# Sheet1.net
KiCad netlist of a schematic drawn in Altium Designer
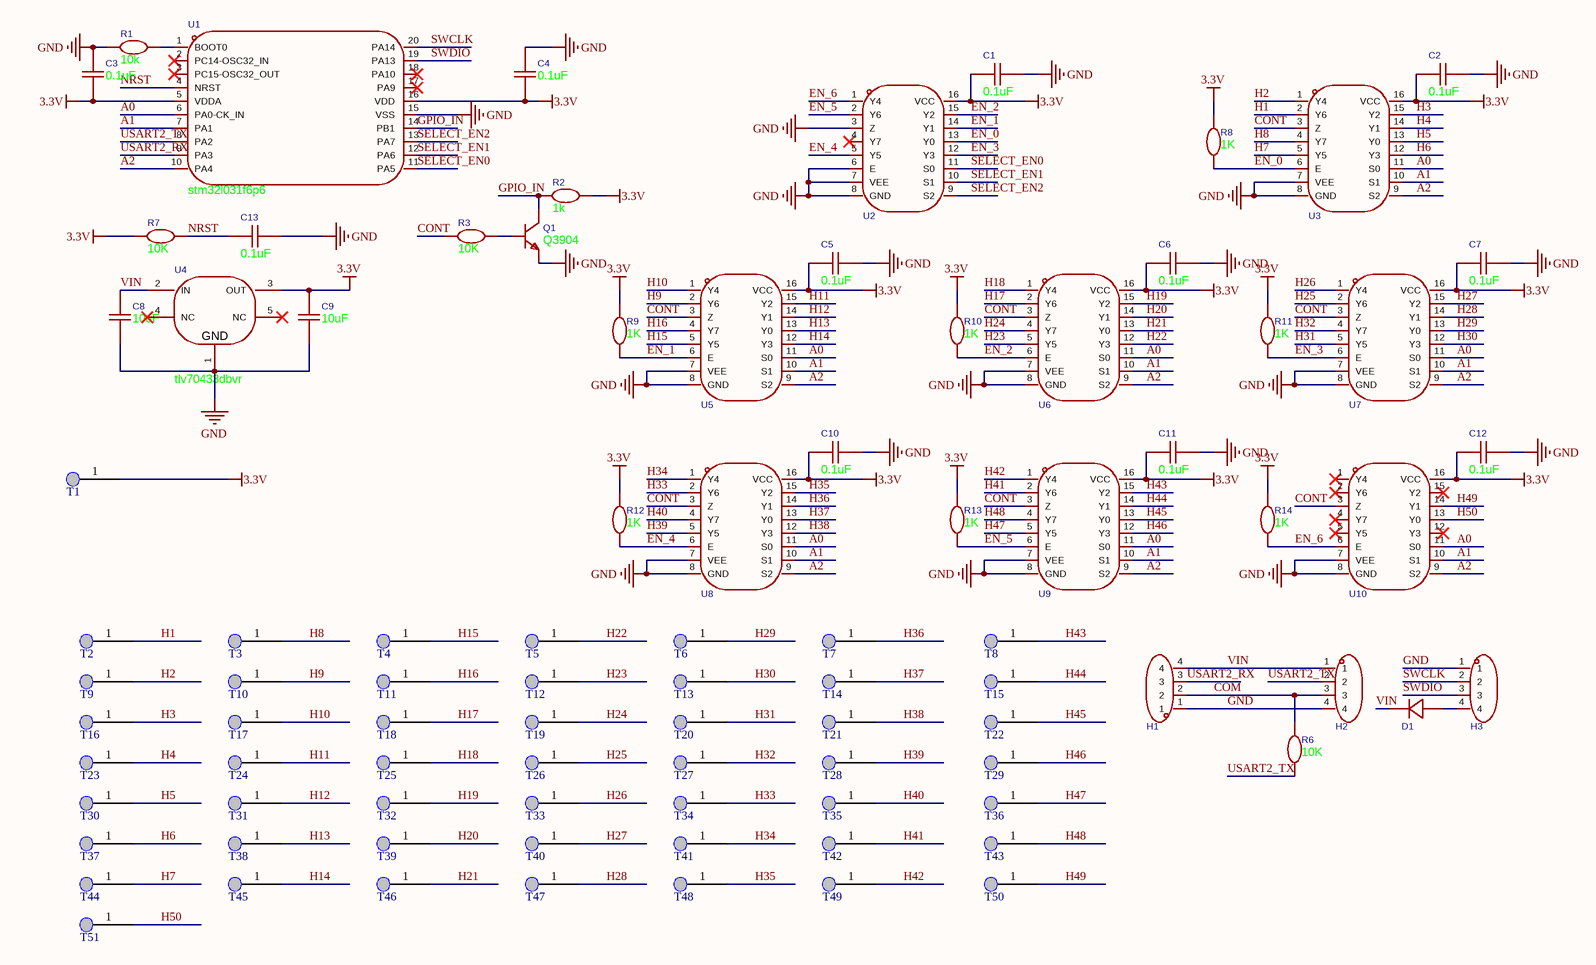
[diagram p0: Sheet1.SchDoc]

(export (version "E")
  (design (tool "Eeschema 10.0.6"))
  (components
    (comp (ref "C1")
      (value "0.1uF")
      (footprint "C0603")
      (description "容值:100nF;精度:±10%;额定电压:50V;温度系数:X7R;")
      (fields (field (name "MANUFACTURER") "SAMSUNG(三星)") (field (name "MANUFACTURERPART") "CL10B104KB8NNNC"))
      (libsource (lib "Schlib1") (part "C"))
    )
    (comp (ref "C2")
      (value "0.1uF")
      (footprint "C0603")
      (description "容值:100nF;精度:±10%;额定电压:50V;温度系数:X7R;")
      (fields (field (name "MANUFACTURER") "SAMSUNG(三星)") (field (name "MANUFACTURERPART") "CL10B104KB8NNNC"))
      (libsource (lib "Schlib1") (part "C"))
    )
    (comp (ref "C3")
      (value "0.1uF")
      (footprint "C0603")
      (description "容值:100nF;精度:±10%;额定电压:50V;温度系数:X7R;")
      (fields (field (name "MANUFACTURER") "SAMSUNG(三星)") (field (name "MANUFACTURERPART") "CL10B104KB8NNNC"))
      (libsource (lib "Schlib1") (part "C"))
    )
    (comp (ref "C4")
      (value "0.1uF")
      (footprint "C0603")
      (description "容值:100nF;精度:±10%;额定电压:50V;温度系数:X7R;")
      (fields (field (name "MANUFACTURER") "SAMSUNG(三星)") (field (name "MANUFACTURERPART") "CL10B104KB8NNNC"))
      (libsource (lib "Schlib1") (part "C"))
    )
    (comp (ref "C5")
      (value "0.1uF")
      (footprint "C0603")
      (description "容值:100nF;精度:±10%;额定电压:50V;温度系数:X7R;")
      (fields (field (name "MANUFACTURER") "SAMSUNG(三星)") (field (name "MANUFACTURERPART") "CL10B104KB8NNNC"))
      (libsource (lib "Schlib1") (part "C"))
    )
    (comp (ref "C6")
      (value "0.1uF")
      (footprint "C0603")
      (description "容值:100nF;精度:±10%;额定电压:50V;温度系数:X7R;")
      (fields (field (name "MANUFACTURER") "SAMSUNG(三星)") (field (name "MANUFACTURERPART") "CL10B104KB8NNNC"))
      (libsource (lib "Schlib1") (part "C"))
    )
    (comp (ref "C7")
      (value "0.1uF")
      (footprint "C0603")
      (description "容值:100nF;精度:±10%;额定电压:50V;温度系数:X7R;")
      (fields (field (name "MANUFACTURER") "SAMSUNG(三星)") (field (name "MANUFACTURERPART") "CL10B104KB8NNNC"))
      (libsource (lib "Schlib1") (part "C"))
    )
    (comp (ref "C8")
      (value "10uF")
      (footprint "C0603")
      (description "容值:100nF;精度:±10%;额定电压:50V;温度系数:X7R;")
      (fields (field (name "MANUFACTURER") "SAMSUNG(三星)") (field (name "MANUFACTURERPART") "CL10B104KB8NNNC"))
      (libsource (lib "Schlib1") (part "C"))
    )
    (comp (ref "C9")
      (value "10uF")
      (footprint "C0603")
      (description "容值:100nF;精度:±10%;额定电压:50V;温度系数:X7R;")
      (fields (field (name "MANUFACTURER") "SAMSUNG(三星)") (field (name "MANUFACTURERPART") "CL10B104KB8NNNC"))
      (libsource (lib "Schlib1") (part "C"))
    )
    (comp (ref "C10")
      (value "0.1uF")
      (footprint "C0603")
      (description "容值:100nF;精度:±10%;额定电压:50V;温度系数:X7R;")
      (fields (field (name "MANUFACTURER") "SAMSUNG(三星)") (field (name "MANUFACTURERPART") "CL10B104KB8NNNC"))
      (libsource (lib "Schlib1") (part "C"))
    )
    (comp (ref "C11")
      (value "0.1uF")
      (footprint "C0603")
      (description "容值:100nF;精度:±10%;额定电压:50V;温度系数:X7R;")
      (fields (field (name "MANUFACTURER") "SAMSUNG(三星)") (field (name "MANUFACTURERPART") "CL10B104KB8NNNC"))
      (libsource (lib "Schlib1") (part "C"))
    )
    (comp (ref "C12")
      (value "0.1uF")
      (footprint "C0603")
      (description "容值:100nF;精度:±10%;额定电压:50V;温度系数:X7R;")
      (fields (field (name "MANUFACTURER") "SAMSUNG(三星)") (field (name "MANUFACTURERPART") "CL10B104KB8NNNC"))
      (libsource (lib "Schlib1") (part "C"))
    )
    (comp (ref "C13")
      (value "0.1uF")
      (footprint "C0603")
      (description "容值:100nF;精度:±10%;额定电压:50V;温度系数:X7R;")
      (fields (field (name "MANUFACTURER") "SAMSUNG(三星)") (field (name "MANUFACTURERPART") "CL10B104KB8NNNC"))
      (libsource (lib "Schlib1") (part "C"))
    )
    (comp (ref "D1")
      (value "1n4148ws_c7420319")
      (footprint "SOD-323_L1.7-W1.3-LS2.5-FD")
      (description "二极管配置:独立式;整流电流:150mA;直流反向耐压(Vr):100V;正向压降(Vf):1.25V@150mA;反向恢复时间(Trr):4ns;")
      (fields (field (name "MANUFACTURER") "R+O(宏嘉诚)") (field (name "MANUFACTURERPART") "1N4148WS"))
      (libsource (lib "Schlib1") (part "1n4148ws_c7420319"))
    )
    (comp (ref "H1")
      (value "pz254v-11-04p")
      (footprint "HDR-TH_4P-P2.54-V-M")
      (fields (field (name "MANUFACTURER") "XFCN(兴飞)") (field (name "MANUFACTURERPART") "PZ254V-11-04P"))
      (libsource (lib "Schlib1") (part "pz254v-11-04p"))
    )
    (comp (ref "H2")
      (value "pz254v-11-04p")
      (footprint "HDR-TH_4P-P2.54-V-M")
      (fields (field (name "MANUFACTURER") "XFCN(兴飞)") (field (name "MANUFACTURERPART") "PZ254V-11-04P"))
      (libsource (lib "Schlib1") (part "pz254v-11-04p"))
    )
    (comp (ref "H3")
      (value "pz254v-11-04p")
      (footprint "HDR-TH_4P-P2.54-V-M")
      (fields (field (name "MANUFACTURER") "XFCN(兴飞)") (field (name "MANUFACTURERPART") "PZ254V-11-04P"))
      (libsource (lib "Schlib1") (part "pz254v-11-04p"))
    )
    (comp (ref "Q1")
      (value "Q3904")
      (footprint "SOT-23-3_L2.9-W1.6-P1.90-LS2.8-BR")
      (description "晶体管类型:NPN;集电极电流(Ic):200mA;集射极击穿电压(Vceo):40V;耗散功率(Pd):225mW;直流电流增益(hFE):40@0.1mA,1.0V;")
      (fields (field (name "MANUFACTURER") "onsemi(安森美)") (field (name "MANUFACTURERPART") "MMBT3904LT1G"))
      (libsource (lib "Schlib1") (part "Q3904"))
    )
    (comp (ref "R1")
      (value "10k")
      (footprint "R0603")
      (description "电阻类型:厚膜电阻;阻值:1kΩ;精度:±1%;功率:100mW;工作电压:75V;温度系数:±100ppm/℃;")
      (fields (field (name "MANUFACTURER") "FOJAN(富捷)") (field (name "MANUFACTURERPART") "FRC0603F1001TS"))
      (libsource (lib "Schlib1") (part "R"))
    )
    (comp (ref "R2")
      (value "1k")
      (footprint "R0603")
      (description "电阻类型:厚膜电阻;阻值:1kΩ;精度:±1%;功率:100mW;工作电压:75V;温度系数:±100ppm/℃;")
      (fields (field (name "MANUFACTURER") "FOJAN(富捷)") (field (name "MANUFACTURERPART") "FRC0603F1001TS"))
      (libsource (lib "Schlib1") (part "R"))
    )
    (comp (ref "R3")
      (value "10K")
      (footprint "R0603")
      (description "电阻类型:厚膜电阻;阻值:1kΩ;精度:±1%;功率:100mW;工作电压:75V;温度系数:±100ppm/℃;")
      (fields (field (name "MANUFACTURER") "FOJAN(富捷)") (field (name "MANUFACTURERPART") "FRC0603F1001TS"))
      (libsource (lib "Schlib1") (part "R"))
    )
    (comp (ref "R6")
      (value "10K")
      (footprint "R0805")
      (description "电阻类型:厚膜电阻;阻值:1kΩ;精度:±1%;功率:100mW;工作电压:75V;温度系数:±100ppm/℃;")
      (fields (field (name "MANUFACTURER") "FOJAN(富捷)") (field (name "MANUFACTURERPART") "FRC0603F1001TS"))
      (libsource (lib "Schlib1") (part "R"))
    )
    (comp (ref "R7")
      (value "10K")
      (footprint "R0603")
      (description "电阻类型:厚膜电阻;阻值:1kΩ;精度:±1%;功率:100mW;工作电压:75V;温度系数:±100ppm/℃;")
      (fields (field (name "MANUFACTURER") "FOJAN(富捷)") (field (name "MANUFACTURERPART") "FRC0603F1001TS"))
      (libsource (lib "Schlib1") (part "R"))
    )
    (comp (ref "R8")
      (value "1K")
      (footprint "R0603")
      (description "电阻类型:厚膜电阻;阻值:1kΩ;精度:±1%;功率:100mW;工作电压:75V;温度系数:±100ppm/℃;")
      (fields (field (name "MANUFACTURER") "FOJAN(富捷)") (field (name "MANUFACTURERPART") "FRC0603F1001TS"))
      (libsource (lib "Schlib1") (part "R"))
    )
    (comp (ref "R9")
      (value "1K")
      (footprint "R0603")
      (description "电阻类型:厚膜电阻;阻值:1kΩ;精度:±1%;功率:100mW;工作电压:75V;温度系数:±100ppm/℃;")
      (fields (field (name "MANUFACTURER") "FOJAN(富捷)") (field (name "MANUFACTURERPART") "FRC0603F1001TS"))
      (libsource (lib "Schlib1") (part "R"))
    )
    (comp (ref "R10")
      (value "1K")
      (footprint "R0603")
      (description "电阻类型:厚膜电阻;阻值:1kΩ;精度:±1%;功率:100mW;工作电压:75V;温度系数:±100ppm/℃;")
      (fields (field (name "MANUFACTURER") "FOJAN(富捷)") (field (name "MANUFACTURERPART") "FRC0603F1001TS"))
      (libsource (lib "Schlib1") (part "R"))
    )
    (comp (ref "R11")
      (value "1K")
      (footprint "R0603")
      (description "电阻类型:厚膜电阻;阻值:1kΩ;精度:±1%;功率:100mW;工作电压:75V;温度系数:±100ppm/℃;")
      (fields (field (name "MANUFACTURER") "FOJAN(富捷)") (field (name "MANUFACTURERPART") "FRC0603F1001TS"))
      (libsource (lib "Schlib1") (part "R"))
    )
    (comp (ref "R12")
      (value "1K")
      (footprint "R0603")
      (description "电阻类型:厚膜电阻;阻值:1kΩ;精度:±1%;功率:100mW;工作电压:75V;温度系数:±100ppm/℃;")
      (fields (field (name "MANUFACTURER") "FOJAN(富捷)") (field (name "MANUFACTURERPART") "FRC0603F1001TS"))
      (libsource (lib "Schlib1") (part "R"))
    )
    (comp (ref "R13")
      (value "1K")
      (footprint "R0603")
      (description "电阻类型:厚膜电阻;阻值:1kΩ;精度:±1%;功率:100mW;工作电压:75V;温度系数:±100ppm/℃;")
      (fields (field (name "MANUFACTURER") "FOJAN(富捷)") (field (name "MANUFACTURERPART") "FRC0603F1001TS"))
      (libsource (lib "Schlib1") (part "R"))
    )
    (comp (ref "R14")
      (value "1K")
      (footprint "R0603")
      (description "电阻类型:厚膜电阻;阻值:1kΩ;精度:±1%;功率:100mW;工作电压:75V;温度系数:±100ppm/℃;")
      (fields (field (name "MANUFACTURER") "FOJAN(富捷)") (field (name "MANUFACTURERPART") "FRC0603F1001TS"))
      (libsource (lib "Schlib1") (part "R"))
    )
    (comp (ref "T1") (value "焊盘") (footprint "Contact") (libsource (lib "Schlib1") (part "PAD")))
    (comp (ref "T2") (value "焊盘") (footprint "Contact") (libsource (lib "Schlib1") (part "PAD")))
    (comp (ref "T3") (value "焊盘") (footprint "Contact") (libsource (lib "Schlib1") (part "PAD")))
    (comp (ref "T4") (value "焊盘") (footprint "Contact") (libsource (lib "Schlib1") (part "PAD")))
    (comp (ref "T5") (value "焊盘") (footprint "Contact") (libsource (lib "Schlib1") (part "PAD")))
    (comp (ref "T6") (value "焊盘") (footprint "Contact") (libsource (lib "Schlib1") (part "PAD")))
    (comp (ref "T7") (value "焊盘") (footprint "Contact") (libsource (lib "Schlib1") (part "PAD")))
    (comp (ref "T8") (value "焊盘") (footprint "Contact") (libsource (lib "Schlib1") (part "PAD")))
    (comp (ref "T9") (value "焊盘") (footprint "Contact") (libsource (lib "Schlib1") (part "PAD")))
    (comp (ref "T10") (value "焊盘") (footprint "Contact") (libsource (lib "Schlib1") (part "PAD")))
    (comp (ref "T11") (value "焊盘") (footprint "Contact") (libsource (lib "Schlib1") (part "PAD")))
    (comp (ref "T12") (value "焊盘") (footprint "Contact") (libsource (lib "Schlib1") (part "PAD")))
    (comp (ref "T13") (value "焊盘") (footprint "Contact") (libsource (lib "Schlib1") (part "PAD")))
    (comp (ref "T14") (value "焊盘") (footprint "Contact") (libsource (lib "Schlib1") (part "PAD")))
    (comp (ref "T15") (value "焊盘") (footprint "Contact") (libsource (lib "Schlib1") (part "PAD")))
    (comp (ref "T16") (value "焊盘") (footprint "Contact") (libsource (lib "Schlib1") (part "PAD")))
    (comp (ref "T17") (value "焊盘") (footprint "Contact") (libsource (lib "Schlib1") (part "PAD")))
    (comp (ref "T18") (value "焊盘") (footprint "Contact") (libsource (lib "Schlib1") (part "PAD")))
    (comp (ref "T19") (value "焊盘") (footprint "Contact") (libsource (lib "Schlib1") (part "PAD")))
    (comp (ref "T20") (value "焊盘") (footprint "Contact") (libsource (lib "Schlib1") (part "PAD")))
    (comp (ref "T21") (value "焊盘") (footprint "Contact") (libsource (lib "Schlib1") (part "PAD")))
    (comp (ref "T22") (value "焊盘") (footprint "Contact") (libsource (lib "Schlib1") (part "PAD")))
    (comp (ref "T23") (value "焊盘") (footprint "Contact") (libsource (lib "Schlib1") (part "PAD")))
    (comp (ref "T24") (value "焊盘") (footprint "Contact") (libsource (lib "Schlib1") (part "PAD")))
    (comp (ref "T25") (value "焊盘") (footprint "Contact") (libsource (lib "Schlib1") (part "PAD")))
    (comp (ref "T26") (value "焊盘") (footprint "Contact") (libsource (lib "Schlib1") (part "PAD")))
    (comp (ref "T27") (value "焊盘") (footprint "Contact") (libsource (lib "Schlib1") (part "PAD")))
    (comp (ref "T28") (value "焊盘") (footprint "Contact") (libsource (lib "Schlib1") (part "PAD")))
    (comp (ref "T29") (value "焊盘") (footprint "Contact") (libsource (lib "Schlib1") (part "PAD")))
    (comp (ref "T30") (value "焊盘") (footprint "Contact") (libsource (lib "Schlib1") (part "PAD")))
    (comp (ref "T31") (value "焊盘") (footprint "Contact") (libsource (lib "Schlib1") (part "PAD")))
    (comp (ref "T32") (value "焊盘") (footprint "Contact") (libsource (lib "Schlib1") (part "PAD")))
    (comp (ref "T33") (value "焊盘") (footprint "Contact") (libsource (lib "Schlib1") (part "PAD")))
    (comp (ref "T34") (value "焊盘") (footprint "Contact") (libsource (lib "Schlib1") (part "PAD")))
    (comp (ref "T35") (value "焊盘") (footprint "Contact") (libsource (lib "Schlib1") (part "PAD")))
    (comp (ref "T36") (value "焊盘") (footprint "Contact") (libsource (lib "Schlib1") (part "PAD")))
    (comp (ref "T37") (value "焊盘") (footprint "Contact") (libsource (lib "Schlib1") (part "PAD")))
    (comp (ref "T38") (value "焊盘") (footprint "Contact") (libsource (lib "Schlib1") (part "PAD")))
    (comp (ref "T39") (value "焊盘") (footprint "Contact") (libsource (lib "Schlib1") (part "PAD")))
    (comp (ref "T40") (value "焊盘") (footprint "Contact") (libsource (lib "Schlib1") (part "PAD")))
    (comp (ref "T41") (value "焊盘") (footprint "Contact") (libsource (lib "Schlib1") (part "PAD")))
    (comp (ref "T42") (value "焊盘") (footprint "Contact") (libsource (lib "Schlib1") (part "PAD")))
    (comp (ref "T43") (value "焊盘") (footprint "Contact") (libsource (lib "Schlib1") (part "PAD")))
    (comp (ref "T44") (value "焊盘") (footprint "Contact") (libsource (lib "Schlib1") (part "PAD")))
    (comp (ref "T45") (value "焊盘") (footprint "Contact") (libsource (lib "Schlib1") (part "PAD")))
    (comp (ref "T46") (value "焊盘") (footprint "Contact") (libsource (lib "Schlib1") (part "PAD")))
    (comp (ref "T47") (value "焊盘") (footprint "Contact") (libsource (lib "Schlib1") (part "PAD")))
    (comp (ref "T48") (value "焊盘") (footprint "Contact") (libsource (lib "Schlib1") (part "PAD")))
    (comp (ref "T49") (value "焊盘") (footprint "Contact") (libsource (lib "Schlib1") (part "PAD")))
    (comp (ref "T50") (value "焊盘") (footprint "Contact") (libsource (lib "Schlib1") (part "PAD")))
    (comp (ref "T51") (value "焊盘") (footprint "Contact") (libsource (lib "Schlib1") (part "PAD")))
    (comp (ref "U1")
      (value "stm32l031f6p6")
      (footprint "TSSOP-20_L6.5-W4.4-P0.65-LS6.4-BL")
      (description "CPU内核:-;CPU最大主频:32MHz;")
      (fields (field (name "MANUFACTURER") "ST(意法半导体)") (field (name "MANUFACTURERPART") "STM32L031F6P6"))
      (libsource (lib "Schlib1") (part "stm32l031f6p6"))
    )
    (comp (ref "U2")
      (value "74hc4051d,653")
      (footprint "SOIC-16_L9.9-W3.9-P1.27-LS6.0-BL")
      (description "开关电路:8:1;通道数:1;导通电阻(Ron):80Ω;")
      (fields (field (name "MANUFACTURER") "Nexperia(安世)") (field (name "MANUFACTURERPART") "74HC4051D,653"))
      (libsource (lib "Schlib1") (part "74hc4051d,653"))
    )
    (comp (ref "U3")
      (value "74hc4051d,653")
      (footprint "SOIC-16_L9.9-W3.9-P1.27-LS6.0-BL")
      (description "开关电路:8:1;通道数:1;导通电阻(Ron):80Ω;")
      (fields (field (name "MANUFACTURER") "Nexperia(安世)") (field (name "MANUFACTURERPART") "74HC4051D,653"))
      (libsource (lib "Schlib1") (part "74hc4051d,653"))
    )
    (comp (ref "U4")
      (value "tlv70433dbvr")
      (footprint "SOT-23-5_L3.0-W1.7-P0.95-LS2.8-BR")
      (description "输出极性:正极;工作电压:24V;输出电压:3.3V;输出电流:150mA;电源纹波抑制比(PSRR):60dB@(100kHz);输出类型:固定;")
      (fields (field (name "MANUFACTURER") "TI(德州仪器)") (field (name "MANUFACTURERPART") "TLV70433DBVR"))
      (libsource (lib "Schlib1") (part "tlv70433dbvr"))
    )
    (comp (ref "U5")
      (value "74hc4051d,653")
      (footprint "SOIC-16_L9.9-W3.9-P1.27-LS6.0-BL")
      (description "开关电路:8:1;通道数:1;导通电阻(Ron):80Ω;")
      (fields (field (name "MANUFACTURER") "Nexperia(安世)") (field (name "MANUFACTURERPART") "74HC4051D,653"))
      (libsource (lib "Schlib1") (part "74hc4051d,653"))
    )
    (comp (ref "U6")
      (value "74hc4051d,653")
      (footprint "SOIC-16_L9.9-W3.9-P1.27-LS6.0-BL")
      (description "开关电路:8:1;通道数:1;导通电阻(Ron):80Ω;")
      (fields (field (name "MANUFACTURER") "Nexperia(安世)") (field (name "MANUFACTURERPART") "74HC4051D,653"))
      (libsource (lib "Schlib1") (part "74hc4051d,653"))
    )
    (comp (ref "U7")
      (value "74hc4051d,653")
      (footprint "SOIC-16_L9.9-W3.9-P1.27-LS6.0-BL")
      (description "开关电路:8:1;通道数:1;导通电阻(Ron):80Ω;")
      (fields (field (name "MANUFACTURER") "Nexperia(安世)") (field (name "MANUFACTURERPART") "74HC4051D,653"))
      (libsource (lib "Schlib1") (part "74hc4051d,653"))
    )
    (comp (ref "U8")
      (value "74hc4051d,653")
      (footprint "SOIC-16_L9.9-W3.9-P1.27-LS6.0-BL")
      (description "开关电路:8:1;通道数:1;导通电阻(Ron):80Ω;")
      (fields (field (name "MANUFACTURER") "Nexperia(安世)") (field (name "MANUFACTURERPART") "74HC4051D,653"))
      (libsource (lib "Schlib1") (part "74hc4051d,653"))
    )
    (comp (ref "U9")
      (value "74hc4051d,653")
      (footprint "SOIC-16_L9.9-W3.9-P1.27-LS6.0-BL")
      (description "开关电路:8:1;通道数:1;导通电阻(Ron):80Ω;")
      (fields (field (name "MANUFACTURER") "Nexperia(安世)") (field (name "MANUFACTURERPART") "74HC4051D,653"))
      (libsource (lib "Schlib1") (part "74hc4051d,653"))
    )
    (comp (ref "U10")
      (value "74hc4051d,653")
      (footprint "SOIC-16_L9.9-W3.9-P1.27-LS6.0-BL")
      (description "开关电路:8:1;通道数:1;导通电阻(Ron):80Ω;")
      (fields (field (name "MANUFACTURER") "Nexperia(安世)") (field (name "MANUFACTURERPART") "74HC4051D,653"))
      (libsource (lib "Schlib1") (part "74hc4051d,653"))
    )
  )
  (nets
    (net (code "1") (name "/A0") (class "Default")
      (node (ref "U1") (pin "6") (pinfunction "PA0-CK_IN_6") (pintype "passive"))
      (node (ref "U10") (pin "11") (pinfunction "S0_11") (pintype "passive"))
      (node (ref "U3") (pin "11") (pinfunction "S0_11") (pintype "passive"))
      (node (ref "U5") (pin "11") (pinfunction "S0_11") (pintype "passive"))
      (node (ref "U6") (pin "11") (pinfunction "S0_11") (pintype "passive"))
      (node (ref "U7") (pin "11") (pinfunction "S0_11") (pintype "passive"))
      (node (ref "U8") (pin "11") (pinfunction "S0_11") (pintype "passive"))
      (node (ref "U9") (pin "11") (pinfunction "S0_11") (pintype "passive"))
    )
    (net (code "2") (name "/A1") (class "Default")
      (node (ref "U1") (pin "7") (pinfunction "PA1_7") (pintype "passive"))
      (node (ref "U10") (pin "10") (pinfunction "S1_10") (pintype "passive"))
      (node (ref "U3") (pin "10") (pinfunction "S1_10") (pintype "passive"))
      (node (ref "U5") (pin "10") (pinfunction "S1_10") (pintype "passive"))
      (node (ref "U6") (pin "10") (pinfunction "S1_10") (pintype "passive"))
      (node (ref "U7") (pin "10") (pinfunction "S1_10") (pintype "passive"))
      (node (ref "U8") (pin "10") (pinfunction "S1_10") (pintype "passive"))
      (node (ref "U9") (pin "10") (pinfunction "S1_10") (pintype "passive"))
    )
    (net (code "3") (name "/A2") (class "Default")
      (node (ref "U1") (pin "10") (pinfunction "PA4_10") (pintype "passive"))
      (node (ref "U10") (pin "9") (pinfunction "S2_9") (pintype "passive"))
      (node (ref "U3") (pin "9") (pinfunction "S2_9") (pintype "passive"))
      (node (ref "U5") (pin "9") (pinfunction "S2_9") (pintype "passive"))
      (node (ref "U6") (pin "9") (pinfunction "S2_9") (pintype "passive"))
      (node (ref "U7") (pin "9") (pinfunction "S2_9") (pintype "passive"))
      (node (ref "U8") (pin "9") (pinfunction "S2_9") (pintype "passive"))
      (node (ref "U9") (pin "9") (pinfunction "S2_9") (pintype "passive"))
    )
    (net (code "4") (name "/COM") (class "Default")
      (node (ref "H1") (pin "2") (pinfunction "2_2") (pintype "passive"))
      (node (ref "H2") (pin "3") (pinfunction "3_3") (pintype "passive"))
      (node (ref "R6") (pin "2") (pinfunction "2_2") (pintype "passive"))
    )
    (net (code "5") (name "/CONT") (class "Default")
      (node (ref "R3") (pin "1") (pinfunction "1_1") (pintype "passive"))
      (node (ref "U10") (pin "3") (pinfunction "Z_3") (pintype "passive"))
      (node (ref "U3") (pin "3") (pinfunction "Z_3") (pintype "passive"))
      (node (ref "U5") (pin "3") (pinfunction "Z_3") (pintype "passive"))
      (node (ref "U6") (pin "3") (pinfunction "Z_3") (pintype "passive"))
      (node (ref "U7") (pin "3") (pinfunction "Z_3") (pintype "passive"))
      (node (ref "U8") (pin "3") (pinfunction "Z_3") (pintype "passive"))
      (node (ref "U9") (pin "3") (pinfunction "Z_3") (pintype "passive"))
    )
    (net (code "6") (name "/EN_0") (class "Default")
      (node (ref "R8") (pin "1") (pinfunction "1_1") (pintype "passive"))
      (node (ref "U2") (pin "13") (pinfunction "Y0_13") (pintype "passive"))
      (node (ref "U3") (pin "6") (pinfunction "E_6") (pintype "passive"))
    )
    (net (code "7") (name "/EN_1") (class "Default")
      (node (ref "R9") (pin "1") (pinfunction "1_1") (pintype "passive"))
      (node (ref "U2") (pin "14") (pinfunction "Y1_14") (pintype "passive"))
      (node (ref "U5") (pin "6") (pinfunction "E_6") (pintype "passive"))
    )
    (net (code "8") (name "/EN_2") (class "Default")
      (node (ref "R10") (pin "1") (pinfunction "1_1") (pintype "passive"))
      (node (ref "U2") (pin "15") (pinfunction "Y2_15") (pintype "passive"))
      (node (ref "U6") (pin "6") (pinfunction "E_6") (pintype "passive"))
    )
    (net (code "9") (name "/EN_3") (class "Default")
      (node (ref "R11") (pin "1") (pinfunction "1_1") (pintype "passive"))
      (node (ref "U2") (pin "12") (pinfunction "Y3_12") (pintype "passive"))
      (node (ref "U7") (pin "6") (pinfunction "E_6") (pintype "passive"))
    )
    (net (code "10") (name "/EN_4") (class "Default")
      (node (ref "R12") (pin "1") (pinfunction "1_1") (pintype "passive"))
      (node (ref "U2") (pin "5") (pinfunction "Y5_5") (pintype "passive"))
      (node (ref "U8") (pin "6") (pinfunction "E_6") (pintype "passive"))
    )
    (net (code "11") (name "/EN_5") (class "Default")
      (node (ref "R13") (pin "1") (pinfunction "1_1") (pintype "passive"))
      (node (ref "U2") (pin "2") (pinfunction "Y6_2") (pintype "passive"))
      (node (ref "U9") (pin "6") (pinfunction "E_6") (pintype "passive"))
    )
    (net (code "12") (name "/EN_6") (class "Default")
      (node (ref "R14") (pin "1") (pinfunction "1_1") (pintype "passive"))
      (node (ref "U10") (pin "6") (pinfunction "E_6") (pintype "passive"))
      (node (ref "U2") (pin "1") (pinfunction "Y4_1") (pintype "passive"))
    )
    (net (code "13") (name "/GPIO_IN") (class "Default")
      (node (ref "Q1") (pin "3") (pinfunction "3_3") (pintype "passive"))
      (node (ref "R2") (pin "2") (pinfunction "2_2") (pintype "passive"))
      (node (ref "U1") (pin "14") (pinfunction "PB1_14") (pintype "passive"))
    )
    (net (code "14") (name "/H1") (class "Default")
      (node (ref "T2") (pin "1") (pintype "passive"))
      (node (ref "U3") (pin "2") (pinfunction "Y6_2") (pintype "passive"))
    )
    (net (code "15") (name "/H2") (class "Default")
      (node (ref "T9") (pin "1") (pintype "passive"))
      (node (ref "U3") (pin "1") (pinfunction "Y4_1") (pintype "passive"))
    )
    (net (code "16") (name "/H3") (class "Default")
      (node (ref "T16") (pin "1") (pintype "passive"))
      (node (ref "U3") (pin "15") (pinfunction "Y2_15") (pintype "passive"))
    )
    (net (code "17") (name "/H4") (class "Default")
      (node (ref "T23") (pin "1") (pintype "passive"))
      (node (ref "U3") (pin "14") (pinfunction "Y1_14") (pintype "passive"))
    )
    (net (code "18") (name "/H5") (class "Default")
      (node (ref "T30") (pin "1") (pintype "passive"))
      (node (ref "U3") (pin "13") (pinfunction "Y0_13") (pintype "passive"))
    )
    (net (code "19") (name "/H6") (class "Default")
      (node (ref "T37") (pin "1") (pintype "passive"))
      (node (ref "U3") (pin "12") (pinfunction "Y3_12") (pintype "passive"))
    )
    (net (code "20") (name "/H7") (class "Default")
      (node (ref "T44") (pin "1") (pintype "passive"))
      (node (ref "U3") (pin "5") (pinfunction "Y5_5") (pintype "passive"))
    )
    (net (code "21") (name "/H8") (class "Default")
      (node (ref "T3") (pin "1") (pintype "passive"))
      (node (ref "U3") (pin "4") (pinfunction "Y7_4") (pintype "passive"))
    )
    (net (code "22") (name "/H9") (class "Default")
      (node (ref "T10") (pin "1") (pintype "passive"))
      (node (ref "U5") (pin "2") (pinfunction "Y6_2") (pintype "passive"))
    )
    (net (code "23") (name "/H10") (class "Default")
      (node (ref "T17") (pin "1") (pintype "passive"))
      (node (ref "U5") (pin "1") (pinfunction "Y4_1") (pintype "passive"))
    )
    (net (code "24") (name "/H11") (class "Default")
      (node (ref "T24") (pin "1") (pintype "passive"))
      (node (ref "U5") (pin "15") (pinfunction "Y2_15") (pintype "passive"))
    )
    (net (code "25") (name "/H12") (class "Default")
      (node (ref "T31") (pin "1") (pintype "passive"))
      (node (ref "U5") (pin "14") (pinfunction "Y1_14") (pintype "passive"))
    )
    (net (code "26") (name "/H13") (class "Default")
      (node (ref "T38") (pin "1") (pintype "passive"))
      (node (ref "U5") (pin "13") (pinfunction "Y0_13") (pintype "passive"))
    )
    (net (code "27") (name "/H14") (class "Default")
      (node (ref "T45") (pin "1") (pintype "passive"))
      (node (ref "U5") (pin "12") (pinfunction "Y3_12") (pintype "passive"))
    )
    (net (code "28") (name "/H15") (class "Default")
      (node (ref "T4") (pin "1") (pintype "passive"))
      (node (ref "U5") (pin "5") (pinfunction "Y5_5") (pintype "passive"))
    )
    (net (code "29") (name "/H16") (class "Default")
      (node (ref "T11") (pin "1") (pintype "passive"))
      (node (ref "U5") (pin "4") (pinfunction "Y7_4") (pintype "passive"))
    )
    (net (code "30") (name "/H17") (class "Default")
      (node (ref "T18") (pin "1") (pintype "passive"))
      (node (ref "U6") (pin "2") (pinfunction "Y6_2") (pintype "passive"))
    )
    (net (code "31") (name "/H18") (class "Default")
      (node (ref "T25") (pin "1") (pintype "passive"))
      (node (ref "U6") (pin "1") (pinfunction "Y4_1") (pintype "passive"))
    )
    (net (code "32") (name "/H19") (class "Default")
      (node (ref "T32") (pin "1") (pintype "passive"))
      (node (ref "U6") (pin "15") (pinfunction "Y2_15") (pintype "passive"))
    )
    (net (code "33") (name "/H20") (class "Default")
      (node (ref "T39") (pin "1") (pintype "passive"))
      (node (ref "U6") (pin "14") (pinfunction "Y1_14") (pintype "passive"))
    )
    (net (code "34") (name "/H21") (class "Default")
      (node (ref "T46") (pin "1") (pintype "passive"))
      (node (ref "U6") (pin "13") (pinfunction "Y0_13") (pintype "passive"))
    )
    (net (code "35") (name "/H22") (class "Default")
      (node (ref "T5") (pin "1") (pintype "passive"))
      (node (ref "U6") (pin "12") (pinfunction "Y3_12") (pintype "passive"))
    )
    (net (code "36") (name "/H23") (class "Default")
      (node (ref "T12") (pin "1") (pintype "passive"))
      (node (ref "U6") (pin "5") (pinfunction "Y5_5") (pintype "passive"))
    )
    (net (code "37") (name "/H24") (class "Default")
      (node (ref "T19") (pin "1") (pintype "passive"))
      (node (ref "U6") (pin "4") (pinfunction "Y7_4") (pintype "passive"))
    )
    (net (code "38") (name "/H25") (class "Default")
      (node (ref "T26") (pin "1") (pintype "passive"))
      (node (ref "U7") (pin "2") (pinfunction "Y6_2") (pintype "passive"))
    )
    (net (code "39") (name "/H26") (class "Default")
      (node (ref "T33") (pin "1") (pintype "passive"))
      (node (ref "U7") (pin "1") (pinfunction "Y4_1") (pintype "passive"))
    )
    (net (code "40") (name "/H27") (class "Default")
      (node (ref "T40") (pin "1") (pintype "passive"))
      (node (ref "U7") (pin "15") (pinfunction "Y2_15") (pintype "passive"))
    )
    (net (code "41") (name "/H28") (class "Default")
      (node (ref "T47") (pin "1") (pintype "passive"))
      (node (ref "U7") (pin "14") (pinfunction "Y1_14") (pintype "passive"))
    )
    (net (code "42") (name "/H29") (class "Default")
      (node (ref "T6") (pin "1") (pintype "passive"))
      (node (ref "U7") (pin "13") (pinfunction "Y0_13") (pintype "passive"))
    )
    (net (code "43") (name "/H30") (class "Default")
      (node (ref "T13") (pin "1") (pintype "passive"))
      (node (ref "U7") (pin "12") (pinfunction "Y3_12") (pintype "passive"))
    )
    (net (code "44") (name "/H31") (class "Default")
      (node (ref "T20") (pin "1") (pintype "passive"))
      (node (ref "U7") (pin "5") (pinfunction "Y5_5") (pintype "passive"))
    )
    (net (code "45") (name "/H32") (class "Default")
      (node (ref "T27") (pin "1") (pintype "passive"))
      (node (ref "U7") (pin "4") (pinfunction "Y7_4") (pintype "passive"))
    )
    (net (code "46") (name "/H33") (class "Default")
      (node (ref "T34") (pin "1") (pintype "passive"))
      (node (ref "U8") (pin "2") (pinfunction "Y6_2") (pintype "passive"))
    )
    (net (code "47") (name "/H34") (class "Default")
      (node (ref "T41") (pin "1") (pintype "passive"))
      (node (ref "U8") (pin "1") (pinfunction "Y4_1") (pintype "passive"))
    )
    (net (code "48") (name "/H35") (class "Default")
      (node (ref "T48") (pin "1") (pintype "passive"))
      (node (ref "U8") (pin "15") (pinfunction "Y2_15") (pintype "passive"))
    )
    (net (code "49") (name "/H36") (class "Default")
      (node (ref "T7") (pin "1") (pintype "passive"))
      (node (ref "U8") (pin "14") (pinfunction "Y1_14") (pintype "passive"))
    )
    (net (code "50") (name "/H37") (class "Default")
      (node (ref "T14") (pin "1") (pintype "passive"))
      (node (ref "U8") (pin "13") (pinfunction "Y0_13") (pintype "passive"))
    )
    (net (code "51") (name "/H38") (class "Default")
      (node (ref "T21") (pin "1") (pintype "passive"))
      (node (ref "U8") (pin "12") (pinfunction "Y3_12") (pintype "passive"))
    )
    (net (code "52") (name "/H39") (class "Default")
      (node (ref "T28") (pin "1") (pintype "passive"))
      (node (ref "U8") (pin "5") (pinfunction "Y5_5") (pintype "passive"))
    )
    (net (code "53") (name "/H40") (class "Default")
      (node (ref "T35") (pin "1") (pintype "passive"))
      (node (ref "U8") (pin "4") (pinfunction "Y7_4") (pintype "passive"))
    )
    (net (code "54") (name "/H41") (class "Default")
      (node (ref "T42") (pin "1") (pintype "passive"))
      (node (ref "U9") (pin "2") (pinfunction "Y6_2") (pintype "passive"))
    )
    (net (code "55") (name "/H42") (class "Default")
      (node (ref "T49") (pin "1") (pintype "passive"))
      (node (ref "U9") (pin "1") (pinfunction "Y4_1") (pintype "passive"))
    )
    (net (code "56") (name "/H43") (class "Default")
      (node (ref "T8") (pin "1") (pintype "passive"))
      (node (ref "U9") (pin "15") (pinfunction "Y2_15") (pintype "passive"))
    )
    (net (code "57") (name "/H44") (class "Default")
      (node (ref "T15") (pin "1") (pintype "passive"))
      (node (ref "U9") (pin "14") (pinfunction "Y1_14") (pintype "passive"))
    )
    (net (code "58") (name "/H45") (class "Default")
      (node (ref "T22") (pin "1") (pintype "passive"))
      (node (ref "U9") (pin "13") (pinfunction "Y0_13") (pintype "passive"))
    )
    (net (code "59") (name "/H46") (class "Default")
      (node (ref "T29") (pin "1") (pintype "passive"))
      (node (ref "U9") (pin "12") (pinfunction "Y3_12") (pintype "passive"))
    )
    (net (code "60") (name "/H47") (class "Default")
      (node (ref "T36") (pin "1") (pintype "passive"))
      (node (ref "U9") (pin "5") (pinfunction "Y5_5") (pintype "passive"))
    )
    (net (code "61") (name "/H48") (class "Default")
      (node (ref "T43") (pin "1") (pintype "passive"))
      (node (ref "U9") (pin "4") (pinfunction "Y7_4") (pintype "passive"))
    )
    (net (code "62") (name "/H49") (class "Default")
      (node (ref "T50") (pin "1") (pintype "passive"))
      (node (ref "U10") (pin "14") (pinfunction "Y1_14") (pintype "passive"))
    )
    (net (code "63") (name "/H50") (class "Default")
      (node (ref "T51") (pin "1") (pintype "passive"))
      (node (ref "U10") (pin "13") (pinfunction "Y0_13") (pintype "passive"))
    )
    (net (code "64") (name "/NRST") (class "Default")
      (node (ref "C13") (pin "1") (pinfunction "1_1") (pintype "passive"))
      (node (ref "R7") (pin "2") (pinfunction "2_2") (pintype "passive"))
      (node (ref "U1") (pin "4") (pinfunction "NRST_4") (pintype "passive"))
    )
    (net (code "65") (name "/SELECT_EN0") (class "Default")
      (node (ref "U1") (pin "11") (pinfunction "PA5_11") (pintype "passive"))
      (node (ref "U2") (pin "11") (pinfunction "S0_11") (pintype "passive"))
    )
    (net (code "66") (name "/SELECT_EN1") (class "Default")
      (node (ref "U1") (pin "12") (pinfunction "PA6_12") (pintype "passive"))
      (node (ref "U2") (pin "10") (pinfunction "S1_10") (pintype "passive"))
    )
    (net (code "67") (name "/SELECT_EN2") (class "Default")
      (node (ref "U1") (pin "13") (pinfunction "PA7_13") (pintype "passive"))
      (node (ref "U2") (pin "9") (pinfunction "S2_9") (pintype "passive"))
    )
    (net (code "68") (name "/SWCLK") (class "Default")
      (node (ref "H3") (pin "2") (pinfunction "2_2") (pintype "passive"))
      (node (ref "U1") (pin "20") (pinfunction "PA14_20") (pintype "passive"))
    )
    (net (code "69") (name "/SWDIO") (class "Default")
      (node (ref "H3") (pin "3") (pinfunction "3_3") (pintype "passive"))
      (node (ref "U1") (pin "19") (pinfunction "PA13_19") (pintype "passive"))
    )
    (net (code "70") (name "/USART2_RX") (class "Default")
      (node (ref "H1") (pin "3") (pinfunction "3_3") (pintype "passive"))
      (node (ref "U1") (pin "9") (pinfunction "PA3_9") (pintype "passive"))
    )
    (net (code "71") (name "/USART2_TX") (class "Default")
      (node (ref "H2") (pin "2") (pinfunction "2_2") (pintype "passive"))
      (node (ref "R6") (pin "1") (pinfunction "1_1") (pintype "passive"))
      (node (ref "U1") (pin "8") (pinfunction "PA2_8") (pintype "passive"))
    )
    (net (code "72") (name "/VIN") (class "Default")
      (node (ref "C8") (pin "2") (pinfunction "2_2") (pintype "passive"))
      (node (ref "D1") (pin "2") (pinfunction "K_2") (pintype "passive"))
      (node (ref "H1") (pin "4") (pinfunction "4_4") (pintype "passive"))
      (node (ref "H2") (pin "1") (pinfunction "1_1") (pintype "passive"))
      (node (ref "U4") (pin "2") (pinfunction "IN_2") (pintype "passive"))
    )
    (net (code "73") (name "3.3V") (class "Default")
      (node (ref "C1") (pin "2") (pinfunction "2_2") (pintype "passive"))
      (node (ref "C10") (pin "2") (pinfunction "2_2") (pintype "passive"))
      (node (ref "C11") (pin "2") (pinfunction "2_2") (pintype "passive"))
      (node (ref "C12") (pin "2") (pinfunction "2_2") (pintype "passive"))
      (node (ref "C2") (pin "2") (pinfunction "2_2") (pintype "passive"))
      (node (ref "C3") (pin "1") (pinfunction "1_1") (pintype "passive"))
      (node (ref "C4") (pin "1") (pinfunction "1_1") (pintype "passive"))
      (node (ref "C5") (pin "2") (pinfunction "2_2") (pintype "passive"))
      (node (ref "C6") (pin "2") (pinfunction "2_2") (pintype "passive"))
      (node (ref "C7") (pin "2") (pinfunction "2_2") (pintype "passive"))
      (node (ref "C9") (pin "2") (pinfunction "2_2") (pintype "passive"))
      (node (ref "R10") (pin "2") (pinfunction "2_2") (pintype "passive"))
      (node (ref "R11") (pin "2") (pinfunction "2_2") (pintype "passive"))
      (node (ref "R12") (pin "2") (pinfunction "2_2") (pintype "passive"))
      (node (ref "R13") (pin "2") (pinfunction "2_2") (pintype "passive"))
      (node (ref "R14") (pin "2") (pinfunction "2_2") (pintype "passive"))
      (node (ref "R2") (pin "1") (pinfunction "1_1") (pintype "passive"))
      (node (ref "R7") (pin "1") (pinfunction "1_1") (pintype "passive"))
      (node (ref "R8") (pin "2") (pinfunction "2_2") (pintype "passive"))
      (node (ref "R9") (pin "2") (pinfunction "2_2") (pintype "passive"))
      (node (ref "T1") (pin "1") (pintype "passive"))
      (node (ref "U1") (pin "16") (pinfunction "VDD_16") (pintype "passive"))
      (node (ref "U1") (pin "5") (pinfunction "VDDA_5") (pintype "passive"))
      (node (ref "U10") (pin "16") (pinfunction "VCC_16") (pintype "passive"))
      (node (ref "U2") (pin "16") (pinfunction "VCC_16") (pintype "passive"))
      (node (ref "U3") (pin "16") (pinfunction "VCC_16") (pintype "passive"))
      (node (ref "U4") (pin "3") (pinfunction "OUT_3") (pintype "passive"))
      (node (ref "U5") (pin "16") (pinfunction "VCC_16") (pintype "passive"))
      (node (ref "U6") (pin "16") (pinfunction "VCC_16") (pintype "passive"))
      (node (ref "U7") (pin "16") (pinfunction "VCC_16") (pintype "passive"))
      (node (ref "U8") (pin "16") (pinfunction "VCC_16") (pintype "passive"))
      (node (ref "U9") (pin "16") (pinfunction "VCC_16") (pintype "passive"))
    )
    (net (code "74") (name "GND") (class "Default")
      (node (ref "C1") (pin "1") (pinfunction "1_1") (pintype "passive"))
      (node (ref "C10") (pin "1") (pinfunction "1_1") (pintype "passive"))
      (node (ref "C11") (pin "1") (pinfunction "1_1") (pintype "passive"))
      (node (ref "C12") (pin "1") (pinfunction "1_1") (pintype "passive"))
      (node (ref "C13") (pin "2") (pinfunction "2_2") (pintype "passive"))
      (node (ref "C2") (pin "1") (pinfunction "1_1") (pintype "passive"))
      (node (ref "C3") (pin "2") (pinfunction "2_2") (pintype "passive"))
      (node (ref "C4") (pin "2") (pinfunction "2_2") (pintype "passive"))
      (node (ref "C5") (pin "1") (pinfunction "1_1") (pintype "passive"))
      (node (ref "C6") (pin "1") (pinfunction "1_1") (pintype "passive"))
      (node (ref "C7") (pin "1") (pinfunction "1_1") (pintype "passive"))
      (node (ref "C8") (pin "1") (pinfunction "1_1") (pintype "passive"))
      (node (ref "C9") (pin "1") (pinfunction "1_1") (pintype "passive"))
      (node (ref "H1") (pin "1") (pinfunction "1_1") (pintype "passive"))
      (node (ref "H2") (pin "4") (pinfunction "4_4") (pintype "passive"))
      (node (ref "H3") (pin "1") (pinfunction "1_1") (pintype "passive"))
      (node (ref "Q1") (pin "2") (pinfunction "2_2") (pintype "passive"))
      (node (ref "R1") (pin "1") (pinfunction "1_1") (pintype "passive"))
      (node (ref "U1") (pin "15") (pinfunction "VSS_15") (pintype "passive"))
      (node (ref "U10") (pin "7") (pinfunction "VEE_7") (pintype "passive"))
      (node (ref "U10") (pin "8") (pinfunction "GND_8") (pintype "passive"))
      (node (ref "U2") (pin "3") (pinfunction "Z_3") (pintype "passive"))
      (node (ref "U2") (pin "6") (pinfunction "E_6") (pintype "passive"))
      (node (ref "U2") (pin "7") (pinfunction "VEE_7") (pintype "passive"))
      (node (ref "U2") (pin "8") (pinfunction "GND_8") (pintype "passive"))
      (node (ref "U3") (pin "7") (pinfunction "VEE_7") (pintype "passive"))
      (node (ref "U3") (pin "8") (pinfunction "GND_8") (pintype "passive"))
      (node (ref "U4") (pin "1") (pinfunction "GND_1") (pintype "passive"))
      (node (ref "U5") (pin "7") (pinfunction "VEE_7") (pintype "passive"))
      (node (ref "U5") (pin "8") (pinfunction "GND_8") (pintype "passive"))
      (node (ref "U6") (pin "7") (pinfunction "VEE_7") (pintype "passive"))
      (node (ref "U6") (pin "8") (pinfunction "GND_8") (pintype "passive"))
      (node (ref "U7") (pin "7") (pinfunction "VEE_7") (pintype "passive"))
      (node (ref "U7") (pin "8") (pinfunction "GND_8") (pintype "passive"))
      (node (ref "U8") (pin "7") (pinfunction "VEE_7") (pintype "passive"))
      (node (ref "U8") (pin "8") (pinfunction "GND_8") (pintype "passive"))
      (node (ref "U9") (pin "7") (pinfunction "VEE_7") (pintype "passive"))
      (node (ref "U9") (pin "8") (pinfunction "GND_8") (pintype "passive"))
    )
    (net (code "75") (name "Net-(D1-A)") (class "Default")
      (node (ref "D1") (pin "1") (pinfunction "A_1") (pintype "passive"))
      (node (ref "H3") (pin "4") (pinfunction "4_4") (pintype "passive"))
    )
    (net (code "76") (name "Net-(Q1-Pad1)") (class "Default")
      (node (ref "Q1") (pin "1") (pinfunction "1_1") (pintype "passive"))
      (node (ref "R3") (pin "2") (pinfunction "2_2") (pintype "passive"))
    )
    (net (code "77") (name "Net-(U1-BOOT0)") (class "Default")
      (node (ref "R1") (pin "2") (pinfunction "2_2") (pintype "passive"))
      (node (ref "U1") (pin "1") (pinfunction "BOOT0_1") (pintype "passive"))
    )
    (net (code "78") (name "unconnected-(U1-PA9-Pad17)") (class "Default")
      (node (ref "U1") (pin "17") (pinfunction "PA9_17") (pintype "passive+no_connect"))
    )
    (net (code "79") (name "unconnected-(U1-PA10-Pad18)") (class "Default")
      (node (ref "U1") (pin "18") (pinfunction "PA10_18") (pintype "passive+no_connect"))
    )
    (net (code "80") (name "unconnected-(U1-PC14-OSC32_IN-Pad2)") (class "Default")
      (node (ref "U1") (pin "2") (pinfunction "PC14-OSC32_IN_2") (pintype "passive+no_connect"))
    )
    (net (code "81") (name "unconnected-(U1-PC15-OSC32_OUT-Pad3)") (class "Default")
      (node (ref "U1") (pin "3") (pinfunction "PC15-OSC32_OUT_3") (pintype "passive+no_connect"))
    )
    (net (code "82") (name "unconnected-(U2-Y7-Pad4)") (class "Default")
      (node (ref "U2") (pin "4") (pinfunction "Y7_4") (pintype "passive+no_connect"))
    )
    (net (code "83") (name "unconnected-(U4-NC-Pad4)") (class "Default")
      (node (ref "U4") (pin "4") (pinfunction "NC_4") (pintype "passive+no_connect"))
    )
    (net (code "84") (name "unconnected-(U4-NC-Pad5)") (class "Default")
      (node (ref "U4") (pin "5") (pinfunction "NC_5") (pintype "passive+no_connect"))
    )
    (net (code "85") (name "unconnected-(U10-Y2-Pad15)") (class "Default")
      (node (ref "U10") (pin "15") (pinfunction "Y2_15") (pintype "passive+no_connect"))
    )
    (net (code "86") (name "unconnected-(U10-Y3-Pad12)") (class "Default")
      (node (ref "U10") (pin "12") (pinfunction "Y3_12") (pintype "passive+no_connect"))
    )
    (net (code "87") (name "unconnected-(U10-Y4-Pad1)") (class "Default")
      (node (ref "U10") (pin "1") (pinfunction "Y4_1") (pintype "passive+no_connect"))
    )
    (net (code "88") (name "unconnected-(U10-Y5-Pad5)") (class "Default")
      (node (ref "U10") (pin "5") (pinfunction "Y5_5") (pintype "passive+no_connect"))
    )
    (net (code "89") (name "unconnected-(U10-Y6-Pad2)") (class "Default")
      (node (ref "U10") (pin "2") (pinfunction "Y6_2") (pintype "passive+no_connect"))
    )
    (net (code "90") (name "unconnected-(U10-Y7-Pad4)") (class "Default")
      (node (ref "U10") (pin "4") (pinfunction "Y7_4") (pintype "passive+no_connect"))
    )
  )
)
